# 555_SCHEMATIC.net
KiCad netlist of a schematic drawn in Altium Designer
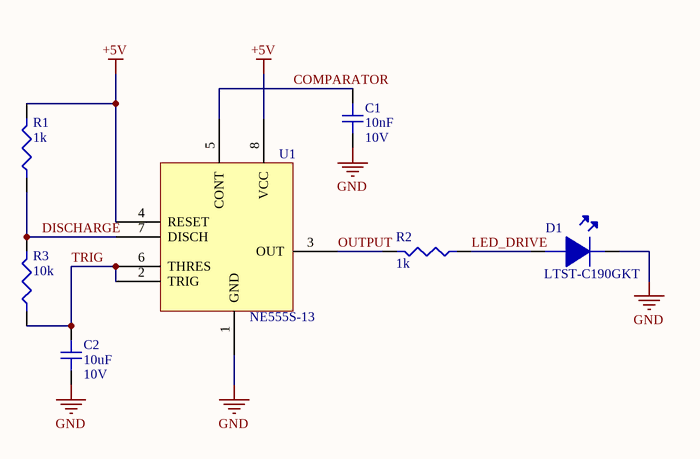
[diagram p0: 555_SCHEMATIC.SchDoc]

(export (version "E")
  (design (tool "Eeschema 10.0.6"))
  (components
    (comp (ref "C1")
      (value "10nF")
      (footprint "C0603")
      (description "Cap Ceramic 0.01uF 10V X7R 10% SMD 0603 125C Paper T/R")
      (fields
        (field (name "MANUFACTURER") "Yageo")
        (field (name "MANUFACTURER PART NUMBER") "CC0603KRX7R6BB103")
        (field (name "VOLTAGE RATING") "10V")
      )
      (libsource (lib "SCH_LIB") (part "CC0603KRX7R6BB103"))
    )
    (comp (ref "C2")
      (value "10uF")
      (footprint "C0603")
      (description "Cap Ceramic 10uF 10V X5R 10% SMD 0603 85C Paper T/R")
      (fields
        (field (name "MANUFACTURER") "Murata")
        (field (name "MANUFACTURER PART NUMBER") "GRM188R61A106KE69D")
        (field (name "VOLTAGE") "10V")
      )
      (libsource (lib "SCH_LIB") (part "GRM188R61A106KE69D"))
    )
    (comp (ref "D1")
      (value "LTST-C190GKT")
      (footprint "LED_0603")
      (description "LED GREEN CLEAR 0603 SMD")
      (fields (field (name "MANUFACTURER") "Vishay Lite-On") (field (name "VOLTAGE") "2V"))
      (libsource (lib "SCH_LIB") (part "LTST-C190GKT"))
    )
    (comp (ref "R1")
      (value "1k")
      (footprint "R0603")
      (description "RES SMD 1K OHM 5% 1/4W 0603")
      (fields (field (name "MANUFACTURER") "Rohm") (field (name "MANUFACTURER PART NUMBER") "ESR03EZPJ102"))
      (libsource (lib "SCH_LIB") (part "ESR03EZPJ102"))
    )
    (comp (ref "R2")
      (value "1k")
      (footprint "R0603")
      (description "RES SMD 1K OHM 5% 1/4W 0603")
      (fields (field (name "MANUFACTURER") "Rohm") (field (name "MANUFACTURER PART NUMBER") "ESR03EZPJ102"))
      (libsource (lib "SCH_LIB") (part "ESR03EZPJ102"))
    )
    (comp (ref "R3")
      (value "10k")
      (footprint "R0603")
      (description "RES SMD 10K OHM 0.5% 1/16W 0816")
      (fields
        (field (name "MANUFACTURER") "Susumu")
        (field (name "MANUFACTURER PART NUMBER") "RR0816P-103-D")
      )
      (libsource (lib "SCH_LIB") (part "RR0816P-103-D"))
    )
    (comp (ref "U1")
      (value "NE555S-13")
      (footprint "SOIC-8")
      (description "555 Type, Timer/Oscillator (Single) IC 500kHz 8-SOIC (0.154\", 3.90mm Width)")
      (fields (field (name "MANUFACTURER") "Diodes"))
      (libsource (lib "SCH_LIB") (part "NE555S-13"))
    )
  )
  (nets
    (net (code "1") (name "+5V") (class "Default")
      (node (ref "R1") (pin "2") (pinfunction "2_2") (pintype "passive"))
      (node (ref "U1") (pin "4") (pinfunction "RESET_4") (pintype "passive"))
      (node (ref "U1") (pin "8") (pinfunction "VCC_8") (pintype "passive"))
    )
    (net (code "2") (name "/COMPARATOR") (class "Default")
      (node (ref "C1") (pin "2") (pinfunction "2_2") (pintype "passive"))
      (node (ref "U1") (pin "5") (pinfunction "CONT_5") (pintype "passive"))
    )
    (net (code "3") (name "/DISCHARGE") (class "Default")
      (node (ref "R1") (pin "1") (pinfunction "1_1") (pintype "passive"))
      (node (ref "R3") (pin "2") (pinfunction "2_2") (pintype "passive"))
      (node (ref "U1") (pin "7") (pinfunction "DISCH_7") (pintype "passive"))
    )
    (net (code "4") (name "/LED_DRIVE") (class "Default")
      (node (ref "D1") (pin "1") (pinfunction "1_1") (pintype "passive"))
      (node (ref "R2") (pin "1") (pinfunction "1_1") (pintype "passive"))
    )
    (net (code "5") (name "/OUTPUT") (class "Default")
      (node (ref "R2") (pin "2") (pinfunction "2_2") (pintype "passive"))
      (node (ref "U1") (pin "3") (pinfunction "OUT_3") (pintype "passive"))
    )
    (net (code "6") (name "/TRIG") (class "Default")
      (node (ref "C2") (pin "2") (pinfunction "2_2") (pintype "passive"))
      (node (ref "R3") (pin "1") (pinfunction "1_1") (pintype "passive"))
      (node (ref "U1") (pin "2") (pinfunction "TRIG_2") (pintype "passive"))
      (node (ref "U1") (pin "6") (pinfunction "THRES_6") (pintype "passive"))
    )
    (net (code "7") (name "GND") (class "Default")
      (node (ref "C1") (pin "1") (pinfunction "1_1") (pintype "passive"))
      (node (ref "C2") (pin "1") (pinfunction "1_1") (pintype "passive"))
      (node (ref "D1") (pin "2") (pinfunction "2_2") (pintype "passive"))
      (node (ref "U1") (pin "1") (pinfunction "GND_1") (pintype "passive"))
    )
  )
)
